# design.net
KiCad netlist of a schematic drawn in Altium Designer
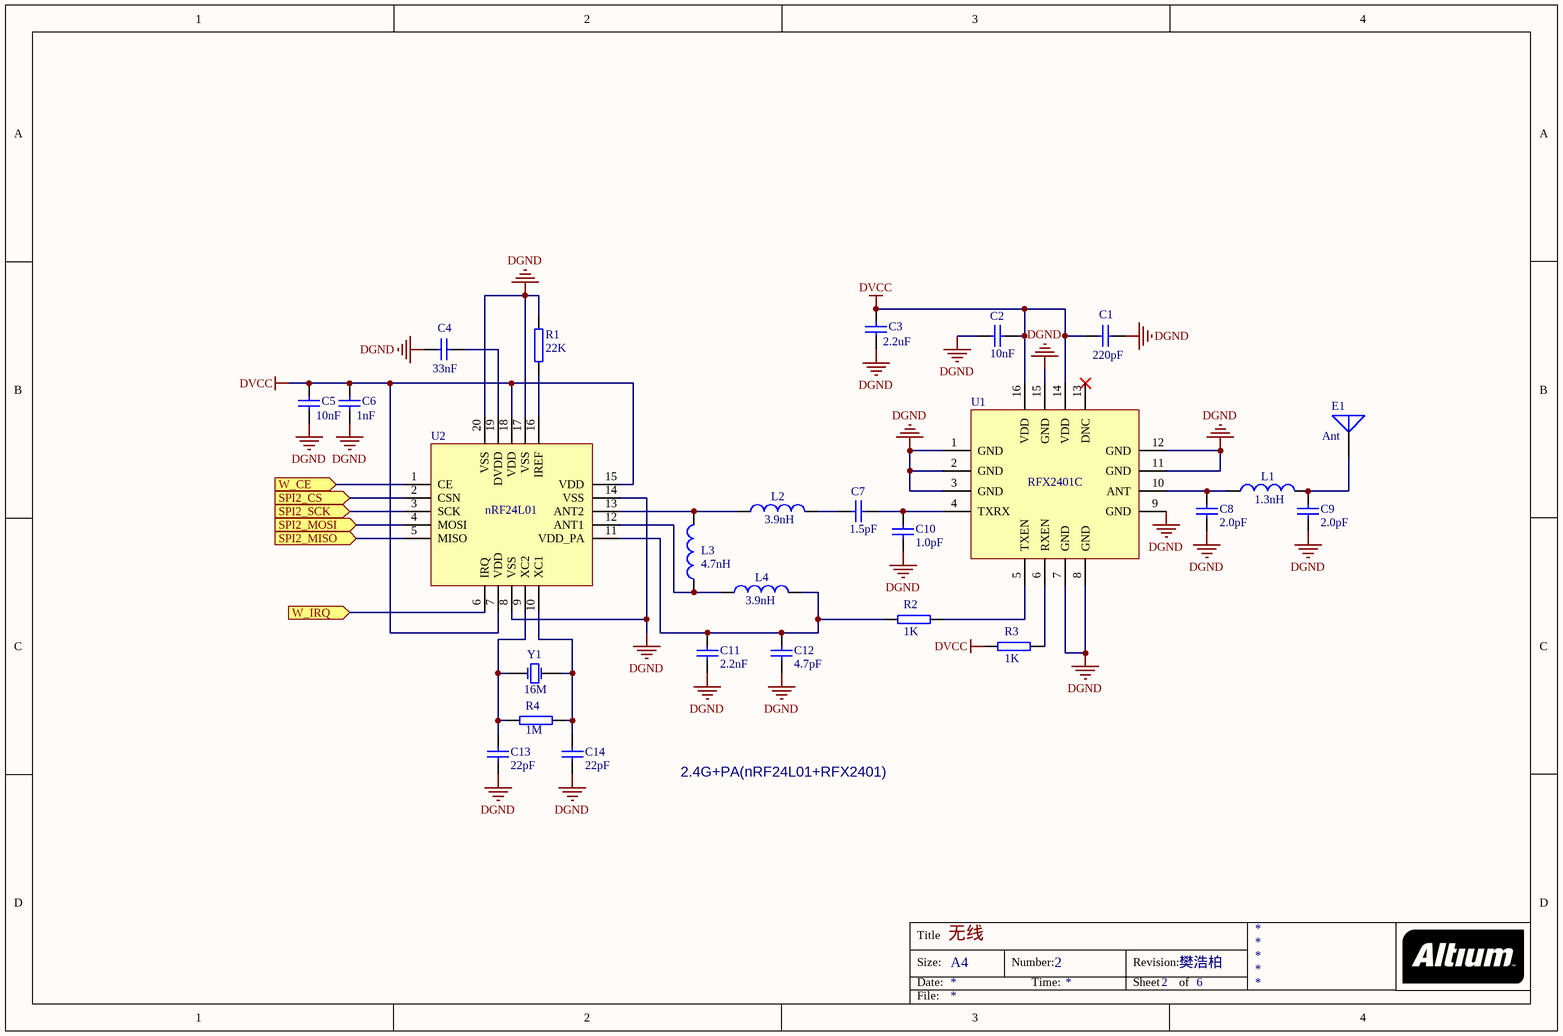
[diagram p0: 无线.SchDoc]

(export (version "E")
  (design (tool "Eeschema 10.0.6"))
  (components
    (comp (ref "C1") (value "220pF") (footprint "CAP-0402") (libsource (lib "Connectors") (part "Cap")))
    (comp (ref "C2") (value "10nF") (footprint "CAP-0402") (libsource (lib "Connectors") (part "Cap")))
    (comp (ref "C3") (value "2.2uF") (footprint "CAP-0402") (libsource (lib "Connectors") (part "Cap")))
    (comp (ref "C4") (value "33nF") (footprint "CAP-0402") (libsource (lib "Connectors") (part "Cap")))
    (comp (ref "C5") (value "10nF") (footprint "CAP-0402") (libsource (lib "Connectors") (part "Cap")))
    (comp (ref "C6") (value "1nF") (footprint "CAP-0402") (libsource (lib "Connectors") (part "Cap")))
    (comp (ref "C7") (value "1.5pF") (footprint "CAP-0402") (libsource (lib "Connectors") (part "Cap")))
    (comp (ref "C8") (value "2.0pF") (footprint "CAP-0402") (libsource (lib "Connectors") (part "Cap")))
    (comp (ref "C9") (value "2.0pF") (footprint "CAP-0402") (libsource (lib "Connectors") (part "Cap")))
    (comp (ref "C10") (value "1.0pF") (footprint "CAP-0402") (libsource (lib "Connectors") (part "Cap")))
    (comp (ref "C11") (value "2.2nF") (footprint "CAP-0402") (libsource (lib "Connectors") (part "Cap")))
    (comp (ref "C12") (value "4.7pF") (footprint "CAP-0402") (libsource (lib "Connectors") (part "Cap")))
    (comp (ref "C13") (value "22pF") (footprint "CAP-0402") (libsource (lib "Connectors") (part "Cap")))
    (comp (ref "C14") (value "22pF") (footprint "CAP-0402") (libsource (lib "Connectors") (part "Cap")))
    (comp (ref "E1") (value "Ant") (footprint "ANT-SMD-5.0mm") (libsource (lib "Connectors") (part "Ant")))
    (comp (ref "L1")
      (value "1.3nH")
      (footprint "Chip Inductor-0402_100505")
      (libsource (lib "Connectors") (part "Inductor"))
    )
    (comp (ref "L2")
      (value "3.9nH")
      (footprint "Chip Inductor-0402_100505")
      (libsource (lib "Connectors") (part "Inductor"))
    )
    (comp (ref "L3")
      (value "4.7nH")
      (footprint "Chip Inductor-0402_100505")
      (libsource (lib "Connectors") (part "Inductor"))
    )
    (comp (ref "L4")
      (value "3.9nH")
      (footprint "Chip Inductor-0402_100505")
      (libsource (lib "Connectors") (part "Inductor"))
    )
    (comp (ref "R1") (value "22K") (footprint "RES-0402") (libsource (lib "Connectors") (part "Res")))
    (comp (ref "R2") (value "1K") (footprint "RES-0402") (libsource (lib "Connectors") (part "Res")))
    (comp (ref "R3") (value "1K") (footprint "RES-0402") (libsource (lib "Connectors") (part "Res")))
    (comp (ref "R4") (value "1M") (footprint "RES-0402") (libsource (lib "Connectors") (part "Res")))
    (comp (ref "U1")
      (value "RFX2401C")
      (footprint "QFN-16-3x3MM")
      (libsource (lib "Devices") (part "RFX2401C"))
    )
    (comp (ref "U2")
      (value "nRF24L01")
      (footprint "QFN-20-4x4mm")
      (libsource (lib "Devices") (part "nRF24L01"))
    )
    (comp (ref "Y1") (value "16M") (footprint "XTAL-OSC-3225") (libsource (lib "Connectors") (part "XTAL")))
  )
  (nets
    (net (code "1") (name "/SPI2_CS") (class "Default")
      (node (ref "U2") (pin "2") (pinfunction "CSN_2") (pintype "passive"))
    )
    (net (code "2") (name "/SPI2_MISO") (class "Default")
      (node (ref "U2") (pin "5") (pinfunction "MISO_5") (pintype "passive"))
    )
    (net (code "3") (name "/SPI2_MOSI") (class "Default")
      (node (ref "U2") (pin "4") (pinfunction "MOSI_4") (pintype "passive"))
    )
    (net (code "4") (name "/SPI2_SCK") (class "Default")
      (node (ref "U2") (pin "3") (pinfunction "SCK_3") (pintype "passive"))
    )
    (net (code "5") (name "/W_CE") (class "Default")
      (node (ref "U2") (pin "1") (pinfunction "CE_1") (pintype "passive"))
    )
    (net (code "6") (name "/W_IRQ") (class "Default")
      (node (ref "U2") (pin "6") (pinfunction "IRQ_6") (pintype "passive"))
    )
    (net (code "7") (name "DGND") (class "Default")
      (node (ref "C1") (pin "1") (pinfunction "1_1") (pintype "passive"))
      (node (ref "C10") (pin "1") (pinfunction "1_1") (pintype "passive"))
      (node (ref "C11") (pin "1") (pinfunction "1_1") (pintype "passive"))
      (node (ref "C12") (pin "1") (pinfunction "1_1") (pintype "passive"))
      (node (ref "C13") (pin "1") (pinfunction "1_1") (pintype "passive"))
      (node (ref "C14") (pin "1") (pinfunction "1_1") (pintype "passive"))
      (node (ref "C2") (pin "2") (pinfunction "2_2") (pintype "passive"))
      (node (ref "C3") (pin "1") (pinfunction "1_1") (pintype "passive"))
      (node (ref "C4") (pin "2") (pinfunction "2_2") (pintype "passive"))
      (node (ref "C5") (pin "1") (pinfunction "1_1") (pintype "passive"))
      (node (ref "C6") (pin "1") (pinfunction "1_1") (pintype "passive"))
      (node (ref "C8") (pin "1") (pinfunction "1_1") (pintype "passive"))
      (node (ref "C9") (pin "1") (pinfunction "1_1") (pintype "passive"))
      (node (ref "R1") (pin "2") (pinfunction "2_2") (pintype "passive"))
      (node (ref "U1") (pin "1") (pinfunction "GND_1") (pintype "passive"))
      (node (ref "U1") (pin "11") (pinfunction "GND_11") (pintype "passive"))
      (node (ref "U1") (pin "12") (pinfunction "GND_12") (pintype "passive"))
      (node (ref "U1") (pin "15") (pinfunction "GND_15") (pintype "passive"))
      (node (ref "U1") (pin "2") (pinfunction "GND_2") (pintype "passive"))
      (node (ref "U1") (pin "3") (pinfunction "GND_3") (pintype "passive"))
      (node (ref "U1") (pin "7") (pinfunction "GND_7") (pintype "passive"))
      (node (ref "U1") (pin "8") (pinfunction "GND_8") (pintype "passive"))
      (node (ref "U1") (pin "9") (pinfunction "GND_9") (pintype "passive"))
      (node (ref "U2") (pin "14") (pinfunction "VSS_14") (pintype "passive"))
      (node (ref "U2") (pin "17") (pinfunction "VSS_17") (pintype "passive"))
      (node (ref "U2") (pin "20") (pinfunction "VSS_20") (pintype "passive"))
      (node (ref "U2") (pin "8") (pinfunction "VSS_8") (pintype "passive"))
    )
    (net (code "8") (name "DVCC") (class "Default")
      (node (ref "C1") (pin "2") (pinfunction "2_2") (pintype "passive"))
      (node (ref "C2") (pin "1") (pinfunction "1_1") (pintype "passive"))
      (node (ref "C3") (pin "2") (pinfunction "2_2") (pintype "passive"))
      (node (ref "C5") (pin "2") (pinfunction "2_2") (pintype "passive"))
      (node (ref "C6") (pin "2") (pinfunction "2_2") (pintype "passive"))
      (node (ref "R3") (pin "2") (pinfunction "2_2") (pintype "passive"))
      (node (ref "U1") (pin "14") (pinfunction "VDD_14") (pintype "passive"))
      (node (ref "U1") (pin "16") (pinfunction "VDD_16") (pintype "passive"))
      (node (ref "U2") (pin "15") (pinfunction "VDD_15") (pintype "passive"))
      (node (ref "U2") (pin "18") (pinfunction "VDD_18") (pintype "passive"))
      (node (ref "U2") (pin "7") (pinfunction "VDD_7") (pintype "passive"))
    )
    (net (code "9") (name "Net-(C7-Pad2)") (class "Default")
      (node (ref "C7") (pin "2") (pinfunction "2_2") (pintype "passive"))
      (node (ref "L2") (pin "2") (pinfunction "2_2") (pintype "passive"))
    )
    (net (code "10") (name "Net-(C9-Pad2)") (class "Default")
      (node (ref "C9") (pin "2") (pinfunction "2_2") (pintype "passive"))
      (node (ref "E1") (pin "1") (pinfunction "1_1") (pintype "passive"))
      (node (ref "L1") (pin "2") (pinfunction "2_2") (pintype "passive"))
    )
    (net (code "11") (name "Net-(U1-ANT)") (class "Default")
      (node (ref "C8") (pin "2") (pinfunction "2_2") (pintype "passive"))
      (node (ref "L1") (pin "1") (pinfunction "1_1") (pintype "passive"))
      (node (ref "U1") (pin "10") (pinfunction "ANT_10") (pintype "passive"))
    )
    (net (code "12") (name "Net-(U1-RXEN)") (class "Default")
      (node (ref "R3") (pin "1") (pinfunction "1_1") (pintype "passive"))
      (node (ref "U1") (pin "6") (pinfunction "RXEN_6") (pintype "passive"))
    )
    (net (code "13") (name "Net-(U1-TXEN)") (class "Default")
      (node (ref "R2") (pin "2") (pinfunction "2_2") (pintype "passive"))
      (node (ref "U1") (pin "5") (pinfunction "TXEN_5") (pintype "passive"))
    )
    (net (code "14") (name "Net-(U1-TXRX)") (class "Default")
      (node (ref "C10") (pin "2") (pinfunction "2_2") (pintype "passive"))
      (node (ref "C7") (pin "1") (pinfunction "1_1") (pintype "passive"))
      (node (ref "U1") (pin "4") (pinfunction "TXRX_4") (pintype "passive"))
    )
    (net (code "15") (name "Net-(U2-ANT1)") (class "Default")
      (node (ref "L3") (pin "1") (pinfunction "1_1") (pintype "passive"))
      (node (ref "L4") (pin "1") (pinfunction "1_1") (pintype "passive"))
      (node (ref "U2") (pin "12") (pinfunction "ANT1_12") (pintype "passive"))
    )
    (net (code "16") (name "Net-(U2-ANT2)") (class "Default")
      (node (ref "L2") (pin "1") (pinfunction "1_1") (pintype "passive"))
      (node (ref "L3") (pin "2") (pinfunction "2_2") (pintype "passive"))
      (node (ref "U2") (pin "13") (pinfunction "ANT2_13") (pintype "passive"))
    )
    (net (code "17") (name "Net-(U2-DVDD)") (class "Default")
      (node (ref "C4") (pin "1") (pinfunction "1_1") (pintype "passive"))
      (node (ref "U2") (pin "19") (pinfunction "DVDD_19") (pintype "passive"))
    )
    (net (code "18") (name "Net-(U2-IREF)") (class "Default")
      (node (ref "R1") (pin "1") (pinfunction "1_1") (pintype "passive"))
      (node (ref "U2") (pin "16") (pinfunction "IREF_16") (pintype "passive"))
    )
    (net (code "19") (name "Net-(U2-VDD_PA)") (class "Default")
      (node (ref "C11") (pin "2") (pinfunction "2_2") (pintype "passive"))
      (node (ref "C12") (pin "2") (pinfunction "2_2") (pintype "passive"))
      (node (ref "L4") (pin "2") (pinfunction "2_2") (pintype "passive"))
      (node (ref "R2") (pin "1") (pinfunction "1_1") (pintype "passive"))
      (node (ref "U2") (pin "11") (pinfunction "VDD_PA_11") (pintype "passive"))
    )
    (net (code "20") (name "Net-(U2-XC1)") (class "Default")
      (node (ref "C14") (pin "2") (pinfunction "2_2") (pintype "passive"))
      (node (ref "R4") (pin "1") (pinfunction "1_1") (pintype "passive"))
      (node (ref "U2") (pin "10") (pinfunction "XC1_10") (pintype "passive"))
      (node (ref "Y1") (pin "3") (pinfunction "OSC2_3") (pintype "passive"))
    )
    (net (code "21") (name "Net-(U2-XC2)") (class "Default")
      (node (ref "C13") (pin "2") (pinfunction "2_2") (pintype "passive"))
      (node (ref "R4") (pin "2") (pinfunction "2_2") (pintype "passive"))
      (node (ref "U2") (pin "9") (pinfunction "XC2_9") (pintype "passive"))
      (node (ref "Y1") (pin "1") (pinfunction "OSC1_1") (pintype "passive"))
    )
    (net (code "22") (name "unconnected-(U1-DNC-Pad13)") (class "Default")
      (node (ref "U1") (pin "13") (pinfunction "DNC_13") (pintype "passive+no_connect"))
    )
  )
)
